# display-controller.net
KiCad netlist of a schematic drawn in EAGLE
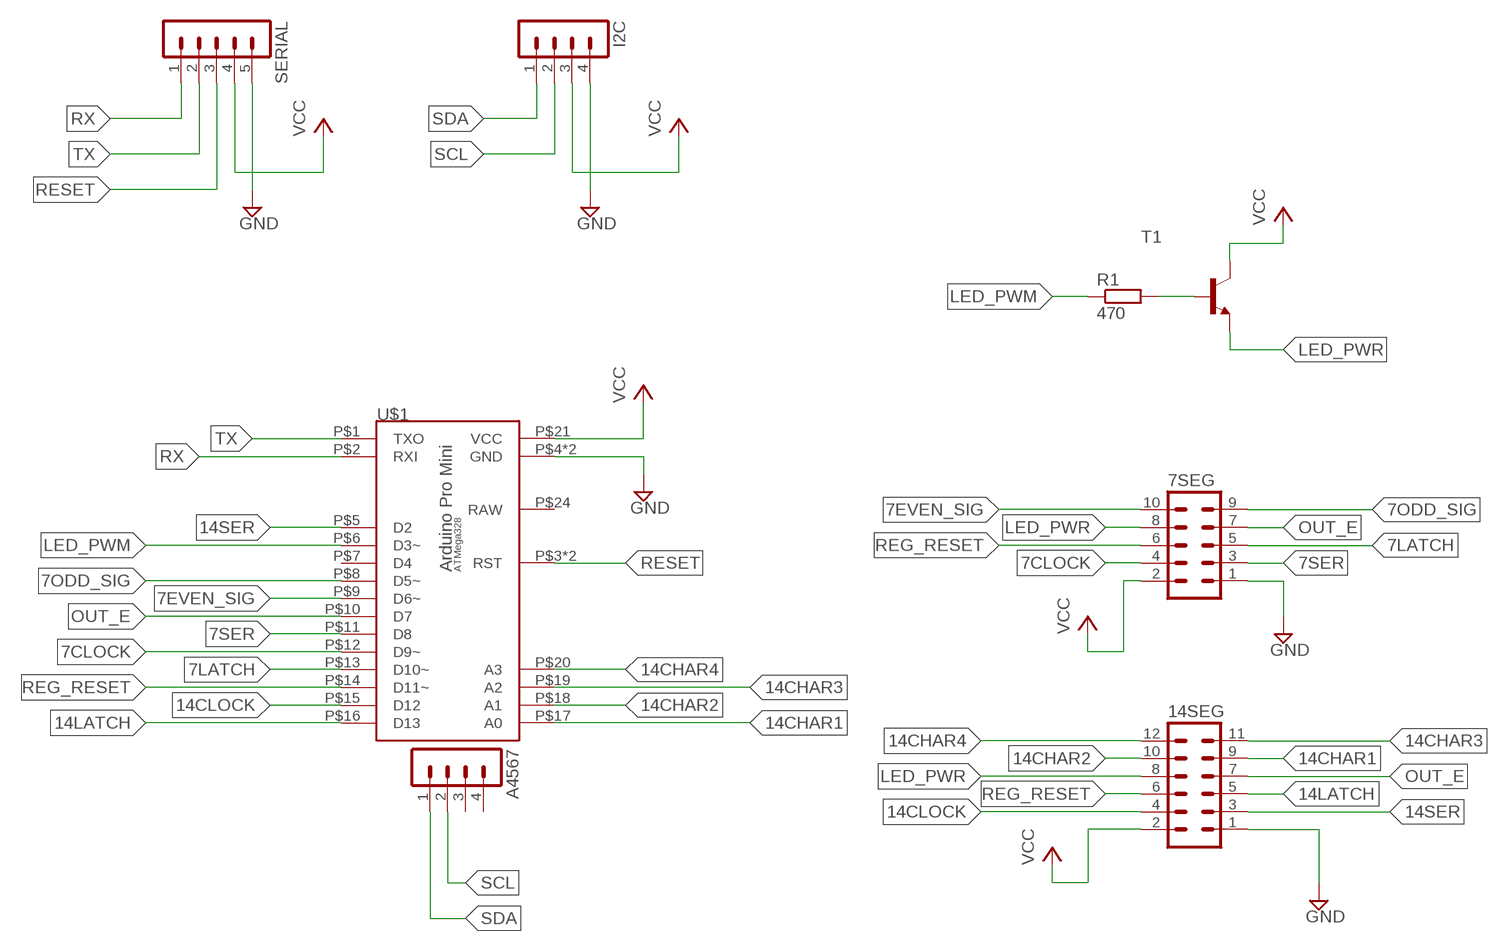
[diagram p0: schematic, sheet 1]

(export (version "E")
  (design (tool "Eeschema 10.0.6"))
  (components
    (comp (ref "7SEG")
      (value "MA05-2")
      (footprint "eagle-import:MA05-2")
      (libsource (lib "eagle-import") (part "MA05-2"))
    )
    (comp (ref "14SEG")
      (value "MA06-2")
      (footprint "eagle-import:MA06-2")
      (libsource (lib "eagle-import") (part "MA06-2"))
    )
    (comp (ref "A4567")
      (value "MA04-1")
      (footprint "eagle-import:MA04-1")
      (libsource (lib "eagle-import") (part "MA04-1"))
    )
    (comp (ref "I2C")
      (value "MA04-1")
      (footprint "eagle-import:MA04-1")
      (libsource (lib "eagle-import") (part "MA04-1"))
    )
    (comp (ref "R1")
      (value "470")
      (footprint "eagle-import:0207_2V")
      (libsource (lib "eagle-import") (part "R-EU_0207/2V"))
    )
    (comp (ref "SERIAL")
      (value "MA05-1")
      (footprint "eagle-import:MA05-1")
      (libsource (lib "eagle-import") (part "MA05-1"))
    )
    (comp (ref "T1")
      (value "BC337-40-NPN-TO92-CBE")
      (footprint "eagle-import:TO92-CBE")
      (libsource (lib "eagle-import") (part "-NPN-TO92-CBEBC337-40"))
    )
    (comp (ref "U$1")
      (value "ARDUINO-PRO-MINI-BARE")
      (footprint "eagle-import:DIP24W")
      (libsource (lib "eagle-import") (part "ARDUINO-PRO-MINI-BARE"))
    )
  )
  (nets
    (net (code "1") (name "7CLOCK") (class "Default")
      (node (ref "7SEG") (pin "4") (pinfunction "4_4") (pintype "passive"))
      (node (ref "U$1") (pin "P$12") (pinfunction "D9~{}_P$12") (pintype "bidirectional"))
    )
    (net (code "2") (name "7EVEN_SIG") (class "Default")
      (node (ref "7SEG") (pin "10") (pinfunction "10_10") (pintype "passive"))
      (node (ref "U$1") (pin "P$9") (pinfunction "D6~{}_P$9") (pintype "bidirectional"))
    )
    (net (code "3") (name "7LATCH") (class "Default")
      (node (ref "7SEG") (pin "5") (pinfunction "5_5") (pintype "passive"))
      (node (ref "U$1") (pin "P$13") (pinfunction "D10~{}_P$13") (pintype "bidirectional"))
    )
    (net (code "4") (name "7ODD_SIG") (class "Default")
      (node (ref "7SEG") (pin "9") (pinfunction "9_9") (pintype "passive"))
      (node (ref "U$1") (pin "P$8") (pinfunction "D5~{}_P$8") (pintype "bidirectional"))
    )
    (net (code "5") (name "7SER") (class "Default")
      (node (ref "7SEG") (pin "3") (pinfunction "3_3") (pintype "passive"))
      (node (ref "U$1") (pin "P$11") (pinfunction "D8_P$11") (pintype "bidirectional"))
    )
    (net (code "6") (name "14CHAR1") (class "Default")
      (node (ref "14SEG") (pin "9") (pinfunction "9_9") (pintype "passive"))
      (node (ref "U$1") (pin "P$17") (pinfunction "A0_P$17") (pintype "bidirectional"))
    )
    (net (code "7") (name "14CHAR2") (class "Default")
      (node (ref "14SEG") (pin "10") (pinfunction "10_10") (pintype "passive"))
      (node (ref "U$1") (pin "P$18") (pinfunction "A1_P$18") (pintype "bidirectional"))
    )
    (net (code "8") (name "14CHAR3") (class "Default")
      (node (ref "14SEG") (pin "11") (pinfunction "11_11") (pintype "passive"))
      (node (ref "U$1") (pin "P$19") (pinfunction "A2_P$19") (pintype "bidirectional"))
    )
    (net (code "9") (name "14CHAR4") (class "Default")
      (node (ref "14SEG") (pin "12") (pinfunction "12_12") (pintype "passive"))
      (node (ref "U$1") (pin "P$20") (pinfunction "A3_P$20") (pintype "bidirectional"))
    )
    (net (code "10") (name "14CLOCK") (class "Default")
      (node (ref "14SEG") (pin "4") (pinfunction "4_4") (pintype "passive"))
      (node (ref "U$1") (pin "P$15") (pinfunction "D12_P$15") (pintype "bidirectional"))
    )
    (net (code "11") (name "14LATCH") (class "Default")
      (node (ref "14SEG") (pin "5") (pinfunction "5_5") (pintype "passive"))
      (node (ref "U$1") (pin "P$16") (pinfunction "D13_P$16") (pintype "bidirectional"))
    )
    (net (code "12") (name "14SER") (class "Default")
      (node (ref "14SEG") (pin "3") (pinfunction "3_3") (pintype "passive"))
      (node (ref "U$1") (pin "P$5") (pinfunction "D2_P$5") (pintype "bidirectional"))
    )
    (net (code "13") (name "GND") (class "Default")
      (node (ref "14SEG") (pin "1") (pinfunction "1_1") (pintype "passive"))
      (node (ref "7SEG") (pin "1") (pinfunction "1_1") (pintype "passive"))
      (node (ref "I2C") (pin "4") (pinfunction "4_4") (pintype "passive"))
      (node (ref "SERIAL") (pin "5") (pinfunction "5_5") (pintype "passive"))
      (node (ref "U$1") (pin "P$23") (pinfunction "GND_P$23") (pintype "bidirectional"))
      (node (ref "U$1") (pin "P$4") (pinfunction "GND_P$4") (pintype "bidirectional"))
    )
    (net (code "14") (name "LED_PWM") (class "Default")
      (node (ref "R1") (pin "1") (pinfunction "1_1") (pintype "passive"))
      (node (ref "U$1") (pin "P$6") (pinfunction "D3~{}_P$6") (pintype "bidirectional"))
    )
    (net (code "15") (name "LED_PWR") (class "Default")
      (node (ref "14SEG") (pin "8") (pinfunction "8_8") (pintype "passive"))
      (node (ref "7SEG") (pin "8") (pinfunction "8_8") (pintype "passive"))
      (node (ref "T1") (pin "E") (pinfunction "E_E") (pintype "passive"))
    )
    (net (code "16") (name "Net-(R1-Pad2)") (class "Default")
      (node (ref "R1") (pin "2") (pinfunction "2_2") (pintype "passive"))
      (node (ref "T1") (pin "B") (pinfunction "B_B") (pintype "passive"))
    )
    (net (code "17") (name "OUT_E") (class "Default")
      (node (ref "14SEG") (pin "7") (pinfunction "7_7") (pintype "passive"))
      (node (ref "7SEG") (pin "7") (pinfunction "7_7") (pintype "passive"))
      (node (ref "U$1") (pin "P$10") (pinfunction "D7_P$10") (pintype "bidirectional"))
    )
    (net (code "18") (name "REG_RESET") (class "Default")
      (node (ref "14SEG") (pin "6") (pinfunction "6_6") (pintype "passive"))
      (node (ref "7SEG") (pin "6") (pinfunction "6_6") (pintype "passive"))
      (node (ref "U$1") (pin "P$14") (pinfunction "D11~{}_P$14") (pintype "bidirectional"))
    )
    (net (code "19") (name "RESET") (class "Default")
      (node (ref "SERIAL") (pin "3") (pinfunction "3_3") (pintype "passive"))
      (node (ref "U$1") (pin "P$22") (pinfunction "RST_P$22") (pintype "bidirectional"))
      (node (ref "U$1") (pin "P$3") (pinfunction "RST_P$3") (pintype "bidirectional"))
    )
    (net (code "20") (name "RX") (class "Default")
      (node (ref "SERIAL") (pin "1") (pinfunction "1_1") (pintype "passive"))
      (node (ref "U$1") (pin "P$2") (pinfunction "RXI_P$2") (pintype "input"))
    )
    (net (code "21") (name "SCL") (class "Default")
      (node (ref "A4567") (pin "2") (pinfunction "2_2") (pintype "passive"))
      (node (ref "I2C") (pin "2") (pinfunction "2_2") (pintype "passive"))
    )
    (net (code "22") (name "SDA") (class "Default")
      (node (ref "A4567") (pin "1") (pinfunction "1_1") (pintype "passive"))
      (node (ref "I2C") (pin "1") (pinfunction "1_1") (pintype "passive"))
    )
    (net (code "23") (name "TX") (class "Default")
      (node (ref "SERIAL") (pin "2") (pinfunction "2_2") (pintype "passive"))
      (node (ref "U$1") (pin "P$1") (pinfunction "TXO_P$1") (pintype "bidirectional"))
    )
    (net (code "24") (name "VCC") (class "Default")
      (node (ref "14SEG") (pin "2") (pinfunction "2_2") (pintype "passive"))
      (node (ref "7SEG") (pin "2") (pinfunction "2_2") (pintype "passive"))
      (node (ref "I2C") (pin "3") (pinfunction "3_3") (pintype "passive"))
      (node (ref "SERIAL") (pin "4") (pinfunction "4_4") (pintype "passive"))
      (node (ref "T1") (pin "C") (pinfunction "C_C") (pintype "passive"))
      (node (ref "U$1") (pin "P$21") (pinfunction "VCC_P$21") (pintype "bidirectional"))
    )
    (net (code "25") (name "unconnected-(A4567-Pad3)") (class "Default")
      (node (ref "A4567") (pin "3") (pinfunction "3_3") (pintype "passive"))
    )
    (net (code "26") (name "unconnected-(A4567-Pad4)") (class "Default")
      (node (ref "A4567") (pin "4") (pinfunction "4_4") (pintype "passive"))
    )
    (net (code "27") (name "unconnected-(U$1-D4-PadP$7)") (class "Default")
      (node (ref "U$1") (pin "P$7") (pinfunction "D4_P$7") (pintype "bidirectional"))
    )
    (net (code "28") (name "unconnected-(U$1-RAW-PadP$24)") (class "Default")
      (node (ref "U$1") (pin "P$24") (pinfunction "RAW_P$24") (pintype "bidirectional"))
    )
  )
)
